# board2.net
KiCad netlist of a schematic drawn in EAGLE
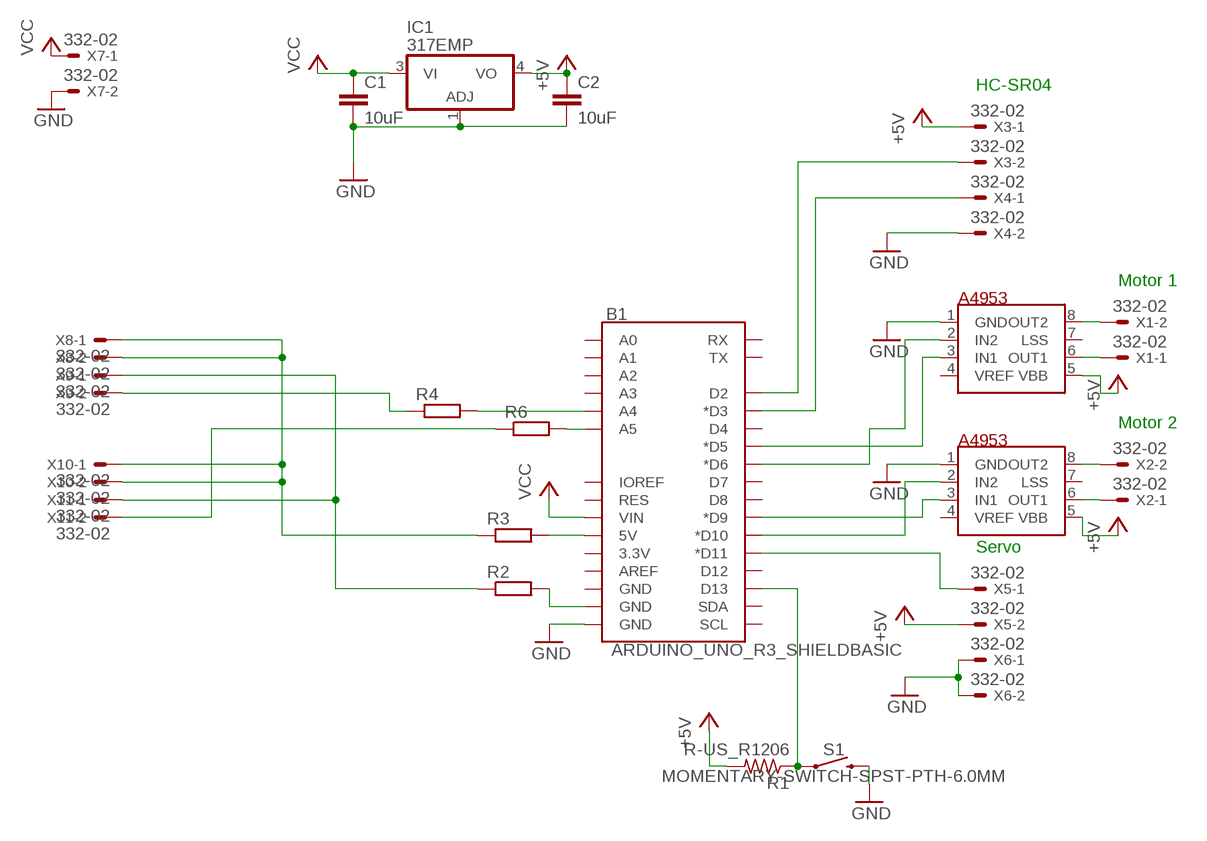
[diagram p0: schematic, sheet 1]

(export (version "E")
  (design (tool "Eeschema 10.0.6"))
  (components
    (comp (ref "A1")
      (value "A4953")
      (footprint "eagle-import:SO08")
      (libsource (lib "eagle-import") (part "A4953"))
    )
    (comp (ref "A2")
      (value "A4953")
      (footprint "eagle-import:SO08")
      (libsource (lib "eagle-import") (part "A4953"))
    )
    (comp (ref "B1")
      (value "ARDUINO_UNO_R3_SHIELDBASIC")
      (footprint "eagle-import:UNO_R3_SHIELD")
      (libsource (lib "eagle-import") (part "ARDUINO_UNO_R3_SHIELDBASIC"))
    )
    (comp (ref "C1")
      (value "10uF")
      (footprint "eagle-import:1206")
      (libsource (lib "eagle-import") (part "10UF-1206-6.3V-20%"))
    )
    (comp (ref "C2")
      (value "10uF")
      (footprint "eagle-import:1206")
      (libsource (lib "eagle-import") (part "10UF-1206-6.3V-20%"))
    )
    (comp (ref "IC1")
      (value "317EMP")
      (footprint "eagle-import:SOT223")
      (libsource (lib "eagle-import") (part "317EMP"))
    )
    (comp (ref "R1")
      (value "R-US_R1206")
      (footprint "eagle-import:R1206")
      (libsource (lib "eagle-import") (part "R-US_R1206"))
    )
    (comp (ref "R2")
      (value "RR1206")
      (footprint "eagle-import:R1206")
      (libsource (lib "eagle-import") (part "RR1206"))
    )
    (comp (ref "R3")
      (value "RR1206")
      (footprint "eagle-import:R1206")
      (libsource (lib "eagle-import") (part "RR1206"))
    )
    (comp (ref "R4")
      (value "RR1206")
      (footprint "eagle-import:R1206")
      (libsource (lib "eagle-import") (part "RR1206"))
    )
    (comp (ref "R6")
      (value "RR1206")
      (footprint "eagle-import:R1206")
      (libsource (lib "eagle-import") (part "RR1206"))
    )
    (comp (ref "S1")
      (value "MOMENTARY-SWITCH-SPST-PTH-6.0MM")
      (footprint "eagle-import:TACTILE_SWITCH_PTH_6.0MM")
      (libsource (lib "eagle-import") (part "MOMENTARY-SWITCH-SPST-PTH-6.0MM"))
    )
    (comp (ref "X1")
      (value "332-02")
      (footprint "eagle-import:332-02")
      (libsource (lib "eagle-import") (part "332-02"))
    )
    (comp (ref "X2")
      (value "332-02")
      (footprint "eagle-import:332-02")
      (libsource (lib "eagle-import") (part "332-02"))
    )
    (comp (ref "X3")
      (value "332-02")
      (footprint "eagle-import:332-02")
      (libsource (lib "eagle-import") (part "332-02"))
    )
    (comp (ref "X4")
      (value "332-02")
      (footprint "eagle-import:332-02")
      (libsource (lib "eagle-import") (part "332-02"))
    )
    (comp (ref "X5")
      (value "332-02")
      (footprint "eagle-import:332-02")
      (libsource (lib "eagle-import") (part "332-02"))
    )
    (comp (ref "X6")
      (value "332-02")
      (footprint "eagle-import:332-02")
      (libsource (lib "eagle-import") (part "332-02"))
    )
    (comp (ref "X7")
      (value "332-02")
      (footprint "eagle-import:332-02")
      (libsource (lib "eagle-import") (part "332-02"))
    )
    (comp (ref "X8")
      (value "332-02")
      (footprint "eagle-import:332-02")
      (libsource (lib "eagle-import") (part "332-02"))
    )
    (comp (ref "X9")
      (value "332-02")
      (footprint "eagle-import:332-02")
      (libsource (lib "eagle-import") (part "332-02"))
    )
    (comp (ref "X10")
      (value "332-02")
      (footprint "eagle-import:332-02")
      (libsource (lib "eagle-import") (part "332-02"))
    )
    (comp (ref "X11")
      (value "332-02")
      (footprint "eagle-import:332-02")
      (libsource (lib "eagle-import") (part "332-02"))
    )
  )
  (nets
    (net (code "1") (name "+5V") (class "Default")
      (node (ref "A1") (pin "5") (pinfunction "VBB_5") (pintype "power_in"))
      (node (ref "A2") (pin "5") (pinfunction "VBB_5") (pintype "power_in"))
      (node (ref "C2") (pin "1") (pinfunction "1_1") (pintype "passive"))
      (node (ref "IC1") (pin "4") (pinfunction "VO_4") (pintype "passive"))
      (node (ref "R1") (pin "2") (pinfunction "2_2") (pintype "passive"))
      (node (ref "X3") (pin "1") (pinfunction "S_1") (pintype "passive"))
      (node (ref "X5") (pin "2") (pinfunction "S_2") (pintype "passive"))
    )
    (net (code "2") (name "GND") (class "Default")
      (node (ref "A1") (pin "1") (pinfunction "GND_1") (pintype "power_in"))
      (node (ref "A2") (pin "1") (pinfunction "GND_1") (pintype "power_in"))
      (node (ref "B1") (pin "GND@0") (pinfunction "GND_GND@0") (pintype "bidirectional"))
      (node (ref "C1") (pin "2") (pinfunction "2_2") (pintype "passive"))
      (node (ref "C2") (pin "2") (pinfunction "2_2") (pintype "passive"))
      (node (ref "IC1") (pin "1") (pinfunction "ADJ_1") (pintype "input"))
      (node (ref "S1") (pin "3") (pinfunction "2_3") (pintype "passive"))
      (node (ref "X4") (pin "2") (pinfunction "S_2") (pintype "passive"))
      (node (ref "X6") (pin "1") (pinfunction "S_1") (pintype "passive"))
      (node (ref "X6") (pin "2") (pinfunction "S_2") (pintype "passive"))
      (node (ref "X7") (pin "2") (pinfunction "S_2") (pintype "passive"))
    )
    (net (code "3") (name "Net-(A1-IN1)") (class "Default")
      (node (ref "A1") (pin "3") (pinfunction "IN1_3") (pintype "input"))
      (node (ref "B1") (pin "D5") (pinfunction "*D5_D5") (pintype "bidirectional"))
    )
    (net (code "4") (name "Net-(A1-IN2)") (class "Default")
      (node (ref "A1") (pin "2") (pinfunction "IN2_2") (pintype "input"))
      (node (ref "B1") (pin "D6") (pinfunction "*D6_D6") (pintype "bidirectional"))
    )
    (net (code "5") (name "Net-(A1-OUT1)") (class "Default")
      (node (ref "A1") (pin "6") (pinfunction "OUT1_6") (pintype "output"))
      (node (ref "X1") (pin "1") (pinfunction "S_1") (pintype "passive"))
    )
    (net (code "6") (name "Net-(A1-OUT2)") (class "Default")
      (node (ref "A1") (pin "8") (pinfunction "OUT2_8") (pintype "output"))
      (node (ref "X1") (pin "2") (pinfunction "S_2") (pintype "passive"))
    )
    (net (code "7") (name "Net-(A2-IN1)") (class "Default")
      (node (ref "A2") (pin "3") (pinfunction "IN1_3") (pintype "input"))
      (node (ref "B1") (pin "D9") (pinfunction "*D9_D9") (pintype "bidirectional"))
    )
    (net (code "8") (name "Net-(A2-IN2)") (class "Default")
      (node (ref "A2") (pin "2") (pinfunction "IN2_2") (pintype "input"))
      (node (ref "B1") (pin "D10") (pinfunction "*D10_D10") (pintype "bidirectional"))
    )
    (net (code "9") (name "Net-(A2-OUT1)") (class "Default")
      (node (ref "A2") (pin "6") (pinfunction "OUT1_6") (pintype "output"))
      (node (ref "X2") (pin "1") (pinfunction "S_1") (pintype "passive"))
    )
    (net (code "10") (name "Net-(A2-OUT2)") (class "Default")
      (node (ref "A2") (pin "8") (pinfunction "OUT2_8") (pintype "output"))
      (node (ref "X2") (pin "2") (pinfunction "S_2") (pintype "passive"))
    )
    (net (code "11") (name "Net-(B1-*D3)") (class "Default")
      (node (ref "B1") (pin "D3") (pinfunction "*D3_D3") (pintype "bidirectional"))
      (node (ref "X4") (pin "1") (pinfunction "S_1") (pintype "passive"))
    )
    (net (code "12") (name "Net-(B1-*D11)") (class "Default")
      (node (ref "B1") (pin "D11") (pinfunction "*D11_D11") (pintype "bidirectional"))
      (node (ref "X5") (pin "1") (pinfunction "S_1") (pintype "passive"))
    )
    (net (code "13") (name "Net-(B1-GND-PadGND@1)") (class "Default")
      (node (ref "B1") (pin "GND@1") (pinfunction "GND_GND@1") (pintype "bidirectional"))
      (node (ref "R2") (pin "2") (pinfunction "2_2") (pintype "passive"))
    )
    (net (code "14") (name "Net-(B1-Pad5V)") (class "Default")
      (node (ref "B1") (pin "5V") (pinfunction "5V_5V") (pintype "bidirectional"))
      (node (ref "R3") (pin "2") (pinfunction "2_2") (pintype "passive"))
    )
    (net (code "15") (name "Net-(B1-PadA4)") (class "Default")
      (node (ref "B1") (pin "A4") (pinfunction "A4_A4") (pintype "bidirectional"))
      (node (ref "R4") (pin "2") (pinfunction "2_2") (pintype "passive"))
    )
    (net (code "16") (name "Net-(B1-PadA5)") (class "Default")
      (node (ref "B1") (pin "A5") (pinfunction "A5_A5") (pintype "bidirectional"))
      (node (ref "R6") (pin "2") (pinfunction "2_2") (pintype "passive"))
    )
    (net (code "17") (name "Net-(B1-PadD13)") (class "Default")
      (node (ref "B1") (pin "D13") (pinfunction "D13_D13") (pintype "bidirectional"))
      (node (ref "R1") (pin "1") (pinfunction "1_1") (pintype "passive"))
      (node (ref "S1") (pin "1") (pinfunction "1_1") (pintype "passive"))
    )
    (net (code "18") (name "Net-(X3B-S)") (class "Default")
      (node (ref "B1") (pin "D2") (pinfunction "D2_D2") (pintype "bidirectional"))
      (node (ref "X3") (pin "2") (pinfunction "S_2") (pintype "passive"))
    )
    (net (code "19") (name "Net-(X9B-S)") (class "Default")
      (node (ref "R4") (pin "1") (pinfunction "1_1") (pintype "passive"))
      (node (ref "X9") (pin "2") (pinfunction "S_2") (pintype "passive"))
    )
    (net (code "20") (name "Net-(X10A-S)") (class "Default")
      (node (ref "R3") (pin "1") (pinfunction "1_1") (pintype "passive"))
      (node (ref "X10") (pin "1") (pinfunction "S_1") (pintype "passive"))
      (node (ref "X10") (pin "2") (pinfunction "S_2") (pintype "passive"))
      (node (ref "X8") (pin "1") (pinfunction "S_1") (pintype "passive"))
      (node (ref "X8") (pin "2") (pinfunction "S_2") (pintype "passive"))
    )
    (net (code "21") (name "Net-(X11A-S)") (class "Default")
      (node (ref "R2") (pin "1") (pinfunction "1_1") (pintype "passive"))
      (node (ref "X11") (pin "1") (pinfunction "S_1") (pintype "passive"))
      (node (ref "X9") (pin "1") (pinfunction "S_1") (pintype "passive"))
    )
    (net (code "22") (name "Net-(X11B-S)") (class "Default")
      (node (ref "R6") (pin "1") (pinfunction "1_1") (pintype "passive"))
      (node (ref "X11") (pin "2") (pinfunction "S_2") (pintype "passive"))
    )
    (net (code "23") (name "VCC") (class "Default")
      (node (ref "B1") (pin "VIN") (pinfunction "VIN_VIN") (pintype "bidirectional"))
      (node (ref "C1") (pin "1") (pinfunction "1_1") (pintype "passive"))
      (node (ref "IC1") (pin "3") (pinfunction "VI_3") (pintype "input"))
      (node (ref "X7") (pin "1") (pinfunction "S_1") (pintype "passive"))
    )
    (net (code "24") (name "unconnected-(A1-LSS-Pad7)") (class "Default")
      (node (ref "A1") (pin "7") (pinfunction "LSS_7") (pintype "input"))
    )
    (net (code "25") (name "unconnected-(A1-VREF-Pad4)") (class "Default")
      (node (ref "A1") (pin "4") (pinfunction "VREF_4") (pintype "input"))
    )
    (net (code "26") (name "unconnected-(A2-LSS-Pad7)") (class "Default")
      (node (ref "A2") (pin "7") (pinfunction "LSS_7") (pintype "input"))
    )
    (net (code "27") (name "unconnected-(A2-VREF-Pad4)") (class "Default")
      (node (ref "A2") (pin "4") (pinfunction "VREF_4") (pintype "input"))
    )
    (net (code "28") (name "unconnected-(B1-GND-PadGND@2)") (class "Default")
      (node (ref "B1") (pin "GND@2") (pinfunction "GND_GND@2") (pintype "bidirectional"))
    )
    (net (code "29") (name "unconnected-(B1-Pad3.3V)") (class "Default")
      (node (ref "B1") (pin "3.3V") (pinfunction "3.3V_3.3V") (pintype "bidirectional"))
    )
    (net (code "30") (name "unconnected-(B1-PadA0)") (class "Default")
      (node (ref "B1") (pin "A0") (pinfunction "A0_A0") (pintype "bidirectional"))
    )
    (net (code "31") (name "unconnected-(B1-PadA1)") (class "Default")
      (node (ref "B1") (pin "A1") (pinfunction "A1_A1") (pintype "bidirectional"))
    )
    (net (code "32") (name "unconnected-(B1-PadA2)") (class "Default")
      (node (ref "B1") (pin "A2") (pinfunction "A2_A2") (pintype "bidirectional"))
    )
    (net (code "33") (name "unconnected-(B1-PadA3)") (class "Default")
      (node (ref "B1") (pin "A3") (pinfunction "A3_A3") (pintype "bidirectional"))
    )
    (net (code "34") (name "unconnected-(B1-PadAREF)") (class "Default")
      (node (ref "B1") (pin "AREF") (pinfunction "AREF_AREF") (pintype "bidirectional"))
    )
    (net (code "35") (name "unconnected-(B1-PadD4)") (class "Default")
      (node (ref "B1") (pin "D4") (pinfunction "D4_D4") (pintype "bidirectional"))
    )
    (net (code "36") (name "unconnected-(B1-PadD7)") (class "Default")
      (node (ref "B1") (pin "D7") (pinfunction "D7_D7") (pintype "bidirectional"))
    )
    (net (code "37") (name "unconnected-(B1-PadD8)") (class "Default")
      (node (ref "B1") (pin "D8") (pinfunction "D8_D8") (pintype "bidirectional"))
    )
    (net (code "38") (name "unconnected-(B1-PadD12)") (class "Default")
      (node (ref "B1") (pin "D12") (pinfunction "D12_D12") (pintype "bidirectional"))
    )
    (net (code "39") (name "unconnected-(B1-PadIOREF)") (class "Default")
      (node (ref "B1") (pin "IOREF") (pinfunction "IOREF_IOREF") (pintype "bidirectional"))
    )
    (net (code "40") (name "unconnected-(B1-PadRES)") (class "Default")
      (node (ref "B1") (pin "RES") (pinfunction "RES_RES") (pintype "bidirectional"))
    )
    (net (code "41") (name "unconnected-(B1-PadRX)") (class "Default")
      (node (ref "B1") (pin "RX") (pinfunction "RX_RX") (pintype "bidirectional"))
    )
    (net (code "42") (name "unconnected-(B1-PadSCL)") (class "Default")
      (node (ref "B1") (pin "SCL") (pinfunction "SCL_SCL") (pintype "bidirectional"))
    )
    (net (code "43") (name "unconnected-(B1-PadSDA)") (class "Default")
      (node (ref "B1") (pin "SDA") (pinfunction "SDA_SDA") (pintype "bidirectional"))
    )
    (net (code "44") (name "unconnected-(B1-PadTX)") (class "Default")
      (node (ref "B1") (pin "TX") (pinfunction "TX_TX") (pintype "bidirectional"))
    )
  )
)
